# mp28164-buck-boost-flashlight-driver-tes.net
KiCad netlist of a schematic drawn in EAGLE
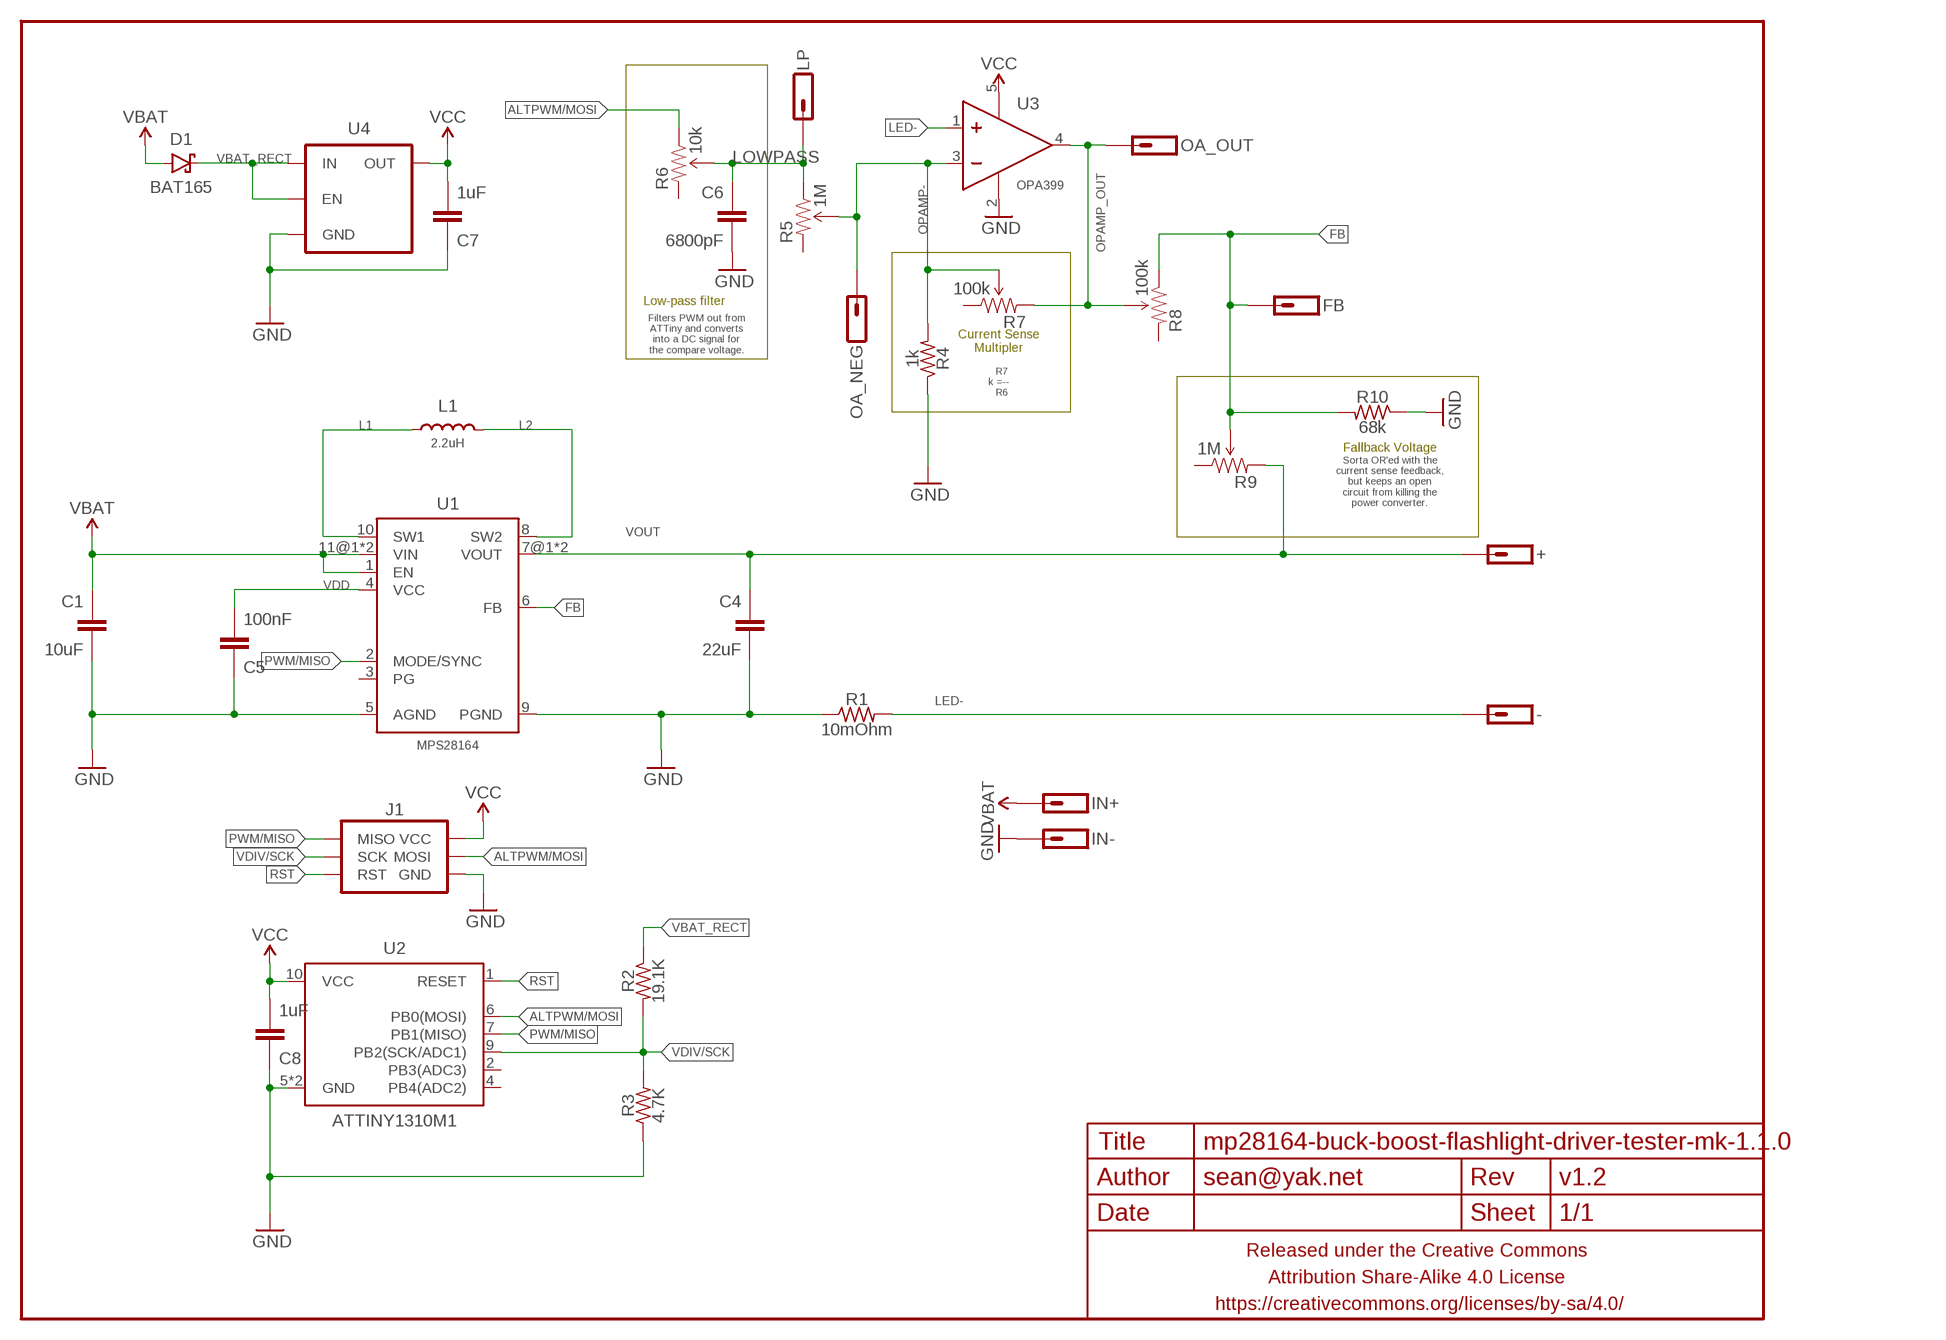
[diagram p0: schematic, sheet 1]

(export (version "E")
  (design (tool "Eeschema 10.0.6"))
  (components
    (comp (ref "+")
      (value "M01PTH-1MM-CIR-NS")
      (footprint "eagle-import:1X01-1MM-CIR-NS")
      (libsource (lib "eagle-import") (part "M01PTH-1MM-CIR-NS"))
    )
    (comp (ref "-")
      (value "M01PTH-1MM-CIR-NS")
      (footprint "eagle-import:1X01-1MM-CIR-NS")
      (libsource (lib "eagle-import") (part "M01PTH-1MM-CIR-NS"))
    )
    (comp (ref "C1")
      (value "10uF")
      (footprint "eagle-import:C1206")
      (libsource (lib "eagle-import") (part "CAPACITOR-CERAMICC1206"))
    )
    (comp (ref "C4")
      (value "22uF")
      (footprint "eagle-import:C1206")
      (libsource (lib "eagle-import") (part "CAPACITOR-CERAMICC1206"))
    )
    (comp (ref "C5")
      (value "100nF")
      (footprint "eagle-import:C0402")
      (libsource (lib "eagle-import") (part "CAPACITOR-CERAMICC0402"))
    )
    (comp (ref "C6")
      (value "6800pF")
      (footprint "eagle-import:C0402")
      (libsource (lib "eagle-import") (part "CAPACITOR-CERAMICC0402"))
    )
    (comp (ref "C7")
      (value "1uF")
      (footprint "eagle-import:C0402")
      (libsource (lib "eagle-import") (part "CAPACITOR-CERAMICC0402"))
    )
    (comp (ref "C8")
      (value "1uF")
      (footprint "eagle-import:C0402")
      (libsource (lib "eagle-import") (part "CAPACITOR-CERAMICC0402"))
    )
    (comp (ref "D1")
      (value "BAT165")
      (footprint "eagle-import:SOD323-SCHOTTKY")
      (libsource (lib "eagle-import") (part "DIODE-SCHOTTKYSOD323"))
    )
    (comp (ref "FB")
      (value "M01SMD-1MM-DIA-NS")
      (footprint "eagle-import:1X01-SMD-1MM-DIA-NS")
      (libsource (lib "eagle-import") (part "M01SMD-1MM-DIA-NS"))
    )
    (comp (ref "FRAME1")
      (value "FRAME-LETTERNO_PACKAGE")
      (footprint "eagle-import:DUMMY")
      (fields
        (field (name "DESIGNER") "sean@yak.net")
        (field (name "VERSION") "v1.2")
        (field (name "DESIGNER_1") "sean@yak.net")
        (field (name "VERSION_1") "v1.2")
      )
      (libsource (lib "eagle-import") (part "FRAME-LETTERNO_PACKAGE"))
    )
    (comp (ref "IN+")
      (value "M01PTH-1MM-CIR-NS")
      (footprint "eagle-import:1X01-1MM-CIR-NS")
      (libsource (lib "eagle-import") (part "M01PTH-1MM-CIR-NS"))
    )
    (comp (ref "IN-")
      (value "M01PTH-1MM-CIR-NS")
      (footprint "eagle-import:1X01-1MM-CIR-NS")
      (libsource (lib "eagle-import") (part "M01PTH-1MM-CIR-NS"))
    )
    (comp (ref "J1")
      (value "AVR_SPI_PRG_6PTH")
      (footprint "eagle-import:2X3")
      (libsource (lib "eagle-import") (part "AVR_SPI_PRG_6PTH"))
    )
    (comp (ref "L1")
      (value "2.2uH")
      (footprint "eagle-import:XAL7070")
      (libsource (lib "eagle-import") (part "INDUCTORXAL7070"))
    )
    (comp (ref "LP")
      (value "M01SMD-1MM-DIA-NS")
      (footprint "eagle-import:1X01-SMD-1MM-DIA-NS")
      (libsource (lib "eagle-import") (part "M01SMD-1MM-DIA-NS"))
    )
    (comp (ref "OA_NEG")
      (value "M01SMD-1MM-DIA-NS")
      (footprint "eagle-import:1X01-SMD-1MM-DIA-NS")
      (libsource (lib "eagle-import") (part "M01SMD-1MM-DIA-NS"))
    )
    (comp (ref "OA_OUT")
      (value "M01SMD-1MM-DIA-NS")
      (footprint "eagle-import:1X01-SMD-1MM-DIA-NS")
      (libsource (lib "eagle-import") (part "M01SMD-1MM-DIA-NS"))
    )
    (comp (ref "R1")
      (value "10mOhm")
      (footprint "eagle-import:R1206")
      (libsource (lib "eagle-import") (part "RESISTORR1206"))
    )
    (comp (ref "R2")
      (value "19.1K")
      (footprint "eagle-import:R0402")
      (libsource (lib "eagle-import") (part "RESISTORR0402"))
    )
    (comp (ref "R3")
      (value "4.7K")
      (footprint "eagle-import:R0402")
      (libsource (lib "eagle-import") (part "RESISTORR0402"))
    )
    (comp (ref "R4")
      (value "1k")
      (footprint "eagle-import:R0402")
      (libsource (lib "eagle-import") (part "RESISTORR0402"))
    )
    (comp (ref "R5")
      (value "1M")
      (footprint "eagle-import:EVM3Y-LESS")
      (libsource (lib "eagle-import") (part "TRIMPOTEVM3Y-LESS"))
    )
    (comp (ref "R6")
      (value "10k")
      (footprint "eagle-import:EVM3Y-LESS")
      (libsource (lib "eagle-import") (part "TRIMPOTEVM3Y-LESS"))
    )
    (comp (ref "R7")
      (value "100k")
      (footprint "eagle-import:EVM3Y-LESS")
      (libsource (lib "eagle-import") (part "TRIMPOTEVM3Y-LESS"))
    )
    (comp (ref "R8")
      (value "100k")
      (footprint "eagle-import:EVM3Y-LESS")
      (libsource (lib "eagle-import") (part "TRIMPOTEVM3Y-LESS"))
    )
    (comp (ref "R9")
      (value "1M")
      (footprint "eagle-import:EVM3Y-LESS")
      (libsource (lib "eagle-import") (part "TRIMPOTEVM3Y-LESS"))
    )
    (comp (ref "R10")
      (value "68k")
      (footprint "eagle-import:R0402")
      (libsource (lib "eagle-import") (part "RESISTORR0402"))
    )
    (comp (ref "U1")
      (value "MPS28164")
      (footprint "eagle-import:MPS28164")
      (libsource (lib "eagle-import") (part "MPS28164"))
    )
    (comp (ref "U2")
      (value "ATTINY1310M1")
      (footprint "eagle-import:QFN10(2X5)")
      (libsource (lib "eagle-import") (part "ATTINY1310M1"))
    )
    (comp (ref "U3")
      (value "OPA399")
      (footprint "eagle-import:SC70")
      (libsource (lib "eagle-import") (part "OPAMPOPA333-SC-70"))
    )
    (comp (ref "U4")
      (value "V_REG_ENTLV700")
      (footprint "eagle-import:SC70")
      (libsource (lib "eagle-import") (part "V_REG_ENTLV700"))
    )
  )
  (nets
    (net (code "1") (name "/L1") (class "Default")
      (node (ref "L1") (pin "P$1") (pinfunction "1_P$1") (pintype "passive"))
      (node (ref "U1") (pin "10") (pinfunction "SW1_10") (pintype "bidirectional"))
    )
    (net (code "2") (name "/L2") (class "Default")
      (node (ref "L1") (pin "P$2") (pinfunction "2_P$2") (pintype "passive"))
      (node (ref "U1") (pin "8") (pinfunction "SW2_8") (pintype "bidirectional"))
    )
    (net (code "3") (name "/LOWPASS") (class "Default")
      (node (ref "C6") (pin "1") (pinfunction "1_1") (pintype "passive"))
      (node (ref "LP") (pin "P$1") (pinfunction "1_P$1") (pintype "passive"))
      (node (ref "R5") (pin "A") (pinfunction "CCW_A") (pintype "passive"))
      (node (ref "R6") (pin "S") (pinfunction "WIPER_S") (pintype "passive"))
    )
    (net (code "4") (name "/OPAMP-") (class "Default")
      (node (ref "OA_NEG") (pin "P$1") (pinfunction "1_P$1") (pintype "passive"))
      (node (ref "R4") (pin "2") (pinfunction "2_2") (pintype "passive"))
      (node (ref "R5") (pin "S") (pinfunction "WIPER_S") (pintype "passive"))
      (node (ref "R7") (pin "S") (pinfunction "WIPER_S") (pintype "passive"))
      (node (ref "U3") (pin "3") (pinfunction "IN-_3") (pintype "input"))
    )
    (net (code "5") (name "/OPAMP_OUT") (class "Default")
      (node (ref "OA_OUT") (pin "P$1") (pinfunction "1_P$1") (pintype "passive"))
      (node (ref "R7") (pin "E") (pinfunction "CW_E") (pintype "passive"))
      (node (ref "R8") (pin "S") (pinfunction "WIPER_S") (pintype "passive"))
      (node (ref "U3") (pin "4") (pinfunction "OUT_4") (pintype "output"))
    )
    (net (code "6") (name "/VDD") (class "Default")
      (node (ref "C5") (pin "2") (pinfunction "2_2") (pintype "passive"))
      (node (ref "U1") (pin "4") (pinfunction "VCC_4") (pintype "bidirectional"))
    )
    (net (code "7") (name "/VOUT") (class "Default")
      (node (ref "+") (pin "1") (pinfunction "1_1") (pintype "passive"))
      (node (ref "C4") (pin "1") (pinfunction "1_1") (pintype "passive"))
      (node (ref "R9") (pin "E") (pinfunction "CW_E") (pintype "passive"))
      (node (ref "U1") (pin "7@1") (pinfunction "VOUT_7@1") (pintype "bidirectional"))
      (node (ref "U1") (pin "7@2") (pinfunction "VOUT_7@2") (pintype "bidirectional"))
    )
    (net (code "8") (name "ALTPWM{slash}MOSI") (class "Default")
      (node (ref "J1") (pin "4") (pinfunction "MOSI_4") (pintype "passive"))
      (node (ref "R6") (pin "A") (pinfunction "CCW_A") (pintype "passive"))
      (node (ref "U2") (pin "6") (pinfunction "PB0(MOSI)_6") (pintype "bidirectional"))
    )
    (net (code "9") (name "FB") (class "Default")
      (node (ref "FB") (pin "P$1") (pinfunction "1_P$1") (pintype "passive"))
      (node (ref "R10") (pin "2") (pinfunction "2_2") (pintype "passive"))
      (node (ref "R8") (pin "A") (pinfunction "CCW_A") (pintype "passive"))
      (node (ref "R9") (pin "S") (pinfunction "WIPER_S") (pintype "passive"))
      (node (ref "U1") (pin "6") (pinfunction "FB_6") (pintype "bidirectional"))
    )
    (net (code "10") (name "GND") (class "Default")
      (node (ref "C1") (pin "2") (pinfunction "2_2") (pintype "passive"))
      (node (ref "C4") (pin "2") (pinfunction "2_2") (pintype "passive"))
      (node (ref "C5") (pin "1") (pinfunction "1_1") (pintype "passive"))
      (node (ref "C6") (pin "2") (pinfunction "2_2") (pintype "passive"))
      (node (ref "C7") (pin "1") (pinfunction "1_1") (pintype "passive"))
      (node (ref "C8") (pin "1") (pinfunction "1_1") (pintype "passive"))
      (node (ref "IN-") (pin "1") (pinfunction "1_1") (pintype "passive"))
      (node (ref "J1") (pin "6") (pinfunction "GND_6") (pintype "passive"))
      (node (ref "R1") (pin "1") (pinfunction "1_1") (pintype "passive"))
      (node (ref "R10") (pin "1") (pinfunction "1_1") (pintype "passive"))
      (node (ref "R3") (pin "1") (pinfunction "1_1") (pintype "passive"))
      (node (ref "R4") (pin "1") (pinfunction "1_1") (pintype "passive"))
      (node (ref "U1") (pin "5") (pinfunction "AGND_5") (pintype "bidirectional"))
      (node (ref "U1") (pin "9") (pinfunction "PGND_9") (pintype "bidirectional"))
      (node (ref "U2") (pin "5") (pinfunction "GND_5") (pintype "bidirectional"))
      (node (ref "U2") (pin "PAD") (pinfunction "GND_PAD") (pintype "bidirectional"))
      (node (ref "U3") (pin "2") (pinfunction "V-_2") (pintype "power_in"))
      (node (ref "U4") (pin "2") (pinfunction "GND_2") (pintype "input"))
    )
    (net (code "11") (name "LED-") (class "Default")
      (node (ref "-") (pin "1") (pinfunction "1_1") (pintype "passive"))
      (node (ref "R1") (pin "2") (pinfunction "2_2") (pintype "passive"))
      (node (ref "U3") (pin "1") (pinfunction "IN+_1") (pintype "input"))
    )
    (net (code "12") (name "PWM{slash}MISO") (class "Default")
      (node (ref "J1") (pin "1") (pinfunction "MISO_1") (pintype "passive"))
      (node (ref "U1") (pin "2") (pinfunction "MODE/SYNC_2") (pintype "bidirectional"))
      (node (ref "U2") (pin "7") (pinfunction "PB1(MISO)_7") (pintype "bidirectional"))
    )
    (net (code "13") (name "RST") (class "Default")
      (node (ref "J1") (pin "5") (pinfunction "RST_5") (pintype "passive"))
      (node (ref "U2") (pin "1") (pinfunction "RESET_1") (pintype "bidirectional"))
    )
    (net (code "14") (name "VBAT") (class "Default")
      (node (ref "C1") (pin "1") (pinfunction "1_1") (pintype "passive"))
      (node (ref "D1") (pin "A") (pinfunction "A_A") (pintype "passive"))
      (node (ref "IN+") (pin "1") (pinfunction "1_1") (pintype "passive"))
      (node (ref "U1") (pin "1") (pinfunction "EN_1") (pintype "bidirectional"))
      (node (ref "U1") (pin "11@1") (pinfunction "VIN_11@1") (pintype "bidirectional"))
      (node (ref "U1") (pin "11@2") (pinfunction "VIN_11@2") (pintype "bidirectional"))
    )
    (net (code "15") (name "VBAT_RECT") (class "Default")
      (node (ref "D1") (pin "C") (pinfunction "C_C") (pintype "passive"))
      (node (ref "R2") (pin "1") (pinfunction "1_1") (pintype "passive"))
      (node (ref "U4") (pin "1") (pinfunction "IN_1") (pintype "input"))
      (node (ref "U4") (pin "3") (pinfunction "EN_3") (pintype "input"))
    )
    (net (code "16") (name "VCC") (class "Default")
      (node (ref "C7") (pin "2") (pinfunction "2_2") (pintype "passive"))
      (node (ref "C8") (pin "2") (pinfunction "2_2") (pintype "passive"))
      (node (ref "J1") (pin "2") (pinfunction "VCC_2") (pintype "passive"))
      (node (ref "U2") (pin "10") (pinfunction "VCC_10") (pintype "bidirectional"))
      (node (ref "U3") (pin "5") (pinfunction "V+_5") (pintype "power_in"))
      (node (ref "U4") (pin "5") (pinfunction "OUT_5") (pintype "passive"))
    )
    (net (code "17") (name "VDIV{slash}SCK") (class "Default")
      (node (ref "J1") (pin "3") (pinfunction "SCK_3") (pintype "passive"))
      (node (ref "R2") (pin "2") (pinfunction "2_2") (pintype "passive"))
      (node (ref "R3") (pin "2") (pinfunction "2_2") (pintype "passive"))
      (node (ref "U2") (pin "9") (pinfunction "PB2(SCK/ADC1)_9") (pintype "bidirectional"))
    )
    (net (code "18") (name "unconnected-(R5-CW-PadE)") (class "Default")
      (node (ref "R5") (pin "E") (pinfunction "CW_E") (pintype "passive"))
    )
    (net (code "19") (name "unconnected-(R6-CW-PadE)") (class "Default")
      (node (ref "R6") (pin "E") (pinfunction "CW_E") (pintype "passive"))
    )
    (net (code "20") (name "unconnected-(R7-CCW-PadA)") (class "Default")
      (node (ref "R7") (pin "A") (pinfunction "CCW_A") (pintype "passive"))
    )
    (net (code "21") (name "unconnected-(R8-CW-PadE)") (class "Default")
      (node (ref "R8") (pin "E") (pinfunction "CW_E") (pintype "passive"))
    )
    (net (code "22") (name "unconnected-(R9-CCW-PadA)") (class "Default")
      (node (ref "R9") (pin "A") (pinfunction "CCW_A") (pintype "passive"))
    )
    (net (code "23") (name "unconnected-(U1-PG-Pad3)") (class "Default")
      (node (ref "U1") (pin "3") (pinfunction "PG_3") (pintype "bidirectional"))
    )
    (net (code "24") (name "unconnected-(U2-PB3(ADC3)-Pad2)") (class "Default")
      (node (ref "U2") (pin "2") (pinfunction "PB3(ADC3)_2") (pintype "bidirectional"))
    )
    (net (code "25") (name "unconnected-(U2-PB4(ADC2)-Pad4)") (class "Default")
      (node (ref "U2") (pin "4") (pinfunction "PB4(ADC2)_4") (pintype "bidirectional"))
    )
  )
)
